# LimitSwitchInterface.net
KiCad netlist of a schematic drawn in EAGLE
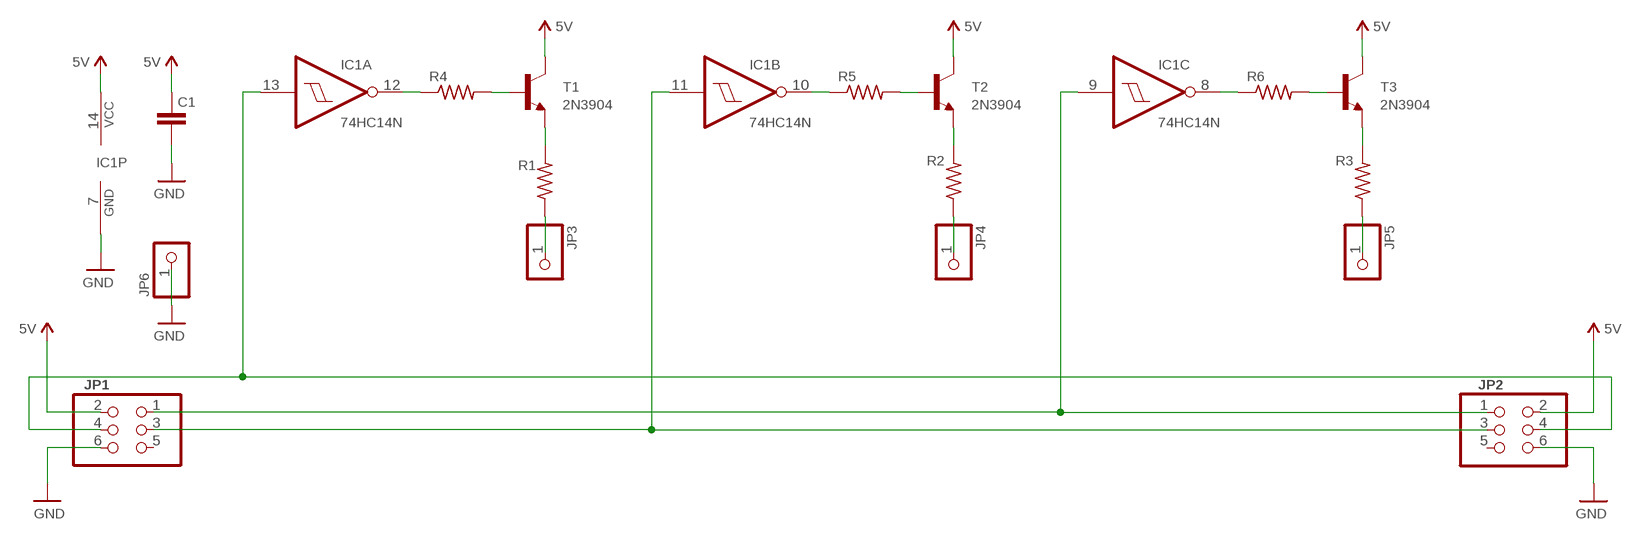
[diagram p0: schematic, sheet 1]

(export (version "E")
  (design (tool "Eeschema 10.0.6"))
  (components
    (comp (ref "C1")
      (value "C-UNPOL")
      (footprint "eagle-import:CAP-PTH-SMALL2")
      (libsource (lib "eagle-import") (part "C-UNPOL"))
    )
    (comp (ref "IC1")
      (value "74HC14N")
      (footprint "eagle-import:DIL14")
      (libsource (lib "eagle-import") (part "7414NHC"))
    )
    (comp (ref "JP1")
      (value "PINHD-2X3")
      (footprint "eagle-import:2X03")
      (libsource (lib "eagle-import") (part "PINHD-2X3"))
    )
    (comp (ref "JP2")
      (value "PINHD-2X3")
      (footprint "eagle-import:2X03")
      (libsource (lib "eagle-import") (part "PINHD-2X3"))
    )
    (comp (ref "JP3")
      (value "PINHD-1X1CB")
      (footprint "eagle-import:1X01-CLEANBIG")
      (libsource (lib "eagle-import") (part "PINHD-1X1CB"))
    )
    (comp (ref "JP4")
      (value "PINHD-1X1CB")
      (footprint "eagle-import:1X01-CLEANBIG")
      (libsource (lib "eagle-import") (part "PINHD-1X1CB"))
    )
    (comp (ref "JP5")
      (value "PINHD-1X1CB")
      (footprint "eagle-import:1X01-CLEANBIG")
      (libsource (lib "eagle-import") (part "PINHD-1X1CB"))
    )
    (comp (ref "JP6")
      (value "PINHD-1X1CB")
      (footprint "eagle-import:1X01-CLEANBIG")
      (libsource (lib "eagle-import") (part "PINHD-1X1CB"))
    )
    (comp (ref "R1")
      (value "RESISTOR-0207/V")
      (footprint "eagle-import:RESISTOR-0207_2V")
      (libsource (lib "eagle-import") (part "RESISTOR-0207/V"))
    )
    (comp (ref "R2")
      (value "RESISTOR-0207/V")
      (footprint "eagle-import:RESISTOR-0207_2V")
      (libsource (lib "eagle-import") (part "RESISTOR-0207/V"))
    )
    (comp (ref "R3")
      (value "RESISTOR-0207/V")
      (footprint "eagle-import:RESISTOR-0207_2V")
      (libsource (lib "eagle-import") (part "RESISTOR-0207/V"))
    )
    (comp (ref "R4")
      (value "RESISTOR-0207/V")
      (footprint "eagle-import:RESISTOR-0207_2V")
      (libsource (lib "eagle-import") (part "RESISTOR-0207/V"))
    )
    (comp (ref "R5")
      (value "RESISTOR-0207/V")
      (footprint "eagle-import:RESISTOR-0207_2V")
      (libsource (lib "eagle-import") (part "RESISTOR-0207/V"))
    )
    (comp (ref "R6")
      (value "RESISTOR-0207/V")
      (footprint "eagle-import:RESISTOR-0207_2V")
      (libsource (lib "eagle-import") (part "RESISTOR-0207/V"))
    )
    (comp (ref "T1")
      (value "2N3904")
      (footprint "eagle-import:2N3904")
      (libsource (lib "eagle-import") (part "2N3904"))
    )
    (comp (ref "T2")
      (value "2N3904")
      (footprint "eagle-import:2N3904")
      (libsource (lib "eagle-import") (part "2N3904"))
    )
    (comp (ref "T3")
      (value "2N3904")
      (footprint "eagle-import:2N3904")
      (libsource (lib "eagle-import") (part "2N3904"))
    )
  )
  (nets
    (net (code "1") (name "5V") (class "Default")
      (node (ref "C1") (pin "1") (pinfunction "1_1") (pintype "passive"))
      (node (ref "IC1") (pin "14") (pinfunction "VCC_14") (pintype "power_in"))
      (node (ref "JP1") (pin "2") (pinfunction "2_2") (pintype "passive"))
      (node (ref "JP2") (pin "2") (pinfunction "2_2") (pintype "passive"))
      (node (ref "T1") (pin "3") (pinfunction "C_3") (pintype "passive"))
      (node (ref "T2") (pin "3") (pinfunction "C_3") (pintype "passive"))
      (node (ref "T3") (pin "3") (pinfunction "C_3") (pintype "passive"))
    )
    (net (code "2") (name "GND") (class "Default")
      (node (ref "C1") (pin "2") (pinfunction "2_2") (pintype "passive"))
      (node (ref "IC1") (pin "7") (pinfunction "GND_7") (pintype "power_in"))
      (node (ref "JP1") (pin "6") (pinfunction "6_6") (pintype "passive"))
      (node (ref "JP2") (pin "6") (pinfunction "6_6") (pintype "passive"))
      (node (ref "JP6") (pin "1") (pinfunction "1_1") (pintype "passive"))
    )
    (net (code "3") (name "Net-(IC1A-I)") (class "Default")
      (node (ref "IC1") (pin "13") (pinfunction "I_13") (pintype "input"))
      (node (ref "JP1") (pin "4") (pinfunction "4_4") (pintype "passive"))
      (node (ref "JP2") (pin "4") (pinfunction "4_4") (pintype "passive"))
    )
    (net (code "4") (name "Net-(IC1A-O)") (class "Default")
      (node (ref "IC1") (pin "12") (pinfunction "O_12") (pintype "output"))
      (node (ref "R4") (pin "1") (pinfunction "1_1") (pintype "passive"))
    )
    (net (code "5") (name "Net-(IC1B-I)") (class "Default")
      (node (ref "IC1") (pin "11") (pinfunction "I_11") (pintype "input"))
      (node (ref "JP1") (pin "3") (pinfunction "3_3") (pintype "passive"))
      (node (ref "JP2") (pin "3") (pinfunction "3_3") (pintype "passive"))
    )
    (net (code "6") (name "Net-(IC1B-O)") (class "Default")
      (node (ref "IC1") (pin "10") (pinfunction "O_10") (pintype "output"))
      (node (ref "R5") (pin "1") (pinfunction "1_1") (pintype "passive"))
    )
    (net (code "7") (name "Net-(IC1C-I)") (class "Default")
      (node (ref "IC1") (pin "9") (pinfunction "I_9") (pintype "input"))
      (node (ref "JP1") (pin "1") (pinfunction "1_1") (pintype "passive"))
      (node (ref "JP2") (pin "1") (pinfunction "1_1") (pintype "passive"))
    )
    (net (code "8") (name "Net-(IC1C-O)") (class "Default")
      (node (ref "IC1") (pin "8") (pinfunction "O_8") (pintype "output"))
      (node (ref "R6") (pin "1") (pinfunction "1_1") (pintype "passive"))
    )
    (net (code "9") (name "Net-(JP3-Pad1)") (class "Default")
      (node (ref "JP3") (pin "1") (pinfunction "1_1") (pintype "passive"))
      (node (ref "R1") (pin "1") (pinfunction "1_1") (pintype "passive"))
    )
    (net (code "10") (name "Net-(JP4-Pad1)") (class "Default")
      (node (ref "JP4") (pin "1") (pinfunction "1_1") (pintype "passive"))
      (node (ref "R2") (pin "1") (pinfunction "1_1") (pintype "passive"))
    )
    (net (code "11") (name "Net-(JP5-Pad1)") (class "Default")
      (node (ref "JP5") (pin "1") (pinfunction "1_1") (pintype "passive"))
      (node (ref "R3") (pin "1") (pinfunction "1_1") (pintype "passive"))
    )
    (net (code "12") (name "Net-(T1-B)") (class "Default")
      (node (ref "R4") (pin "2") (pinfunction "2_2") (pintype "passive"))
      (node (ref "T1") (pin "2") (pinfunction "B_2") (pintype "passive"))
    )
    (net (code "13") (name "Net-(T1-E)") (class "Default")
      (node (ref "R1") (pin "2") (pinfunction "2_2") (pintype "passive"))
      (node (ref "T1") (pin "1") (pinfunction "E_1") (pintype "passive"))
    )
    (net (code "14") (name "Net-(T2-B)") (class "Default")
      (node (ref "R5") (pin "2") (pinfunction "2_2") (pintype "passive"))
      (node (ref "T2") (pin "2") (pinfunction "B_2") (pintype "passive"))
    )
    (net (code "15") (name "Net-(T2-E)") (class "Default")
      (node (ref "R2") (pin "2") (pinfunction "2_2") (pintype "passive"))
      (node (ref "T2") (pin "1") (pinfunction "E_1") (pintype "passive"))
    )
    (net (code "16") (name "Net-(T3-B)") (class "Default")
      (node (ref "R6") (pin "2") (pinfunction "2_2") (pintype "passive"))
      (node (ref "T3") (pin "2") (pinfunction "B_2") (pintype "passive"))
    )
    (net (code "17") (name "Net-(T3-E)") (class "Default")
      (node (ref "R3") (pin "2") (pinfunction "2_2") (pintype "passive"))
      (node (ref "T3") (pin "1") (pinfunction "E_1") (pintype "passive"))
    )
    (net (code "18") (name "unconnected-(JP1-Pad5)") (class "Default")
      (node (ref "JP1") (pin "5") (pinfunction "5_5") (pintype "passive"))
    )
    (net (code "19") (name "unconnected-(JP2-Pad5)") (class "Default")
      (node (ref "JP2") (pin "5") (pinfunction "5_5") (pintype "passive"))
    )
  )
)
